# DSI_LCD.net
KiCad netlist of a schematic drawn in Altium Designer
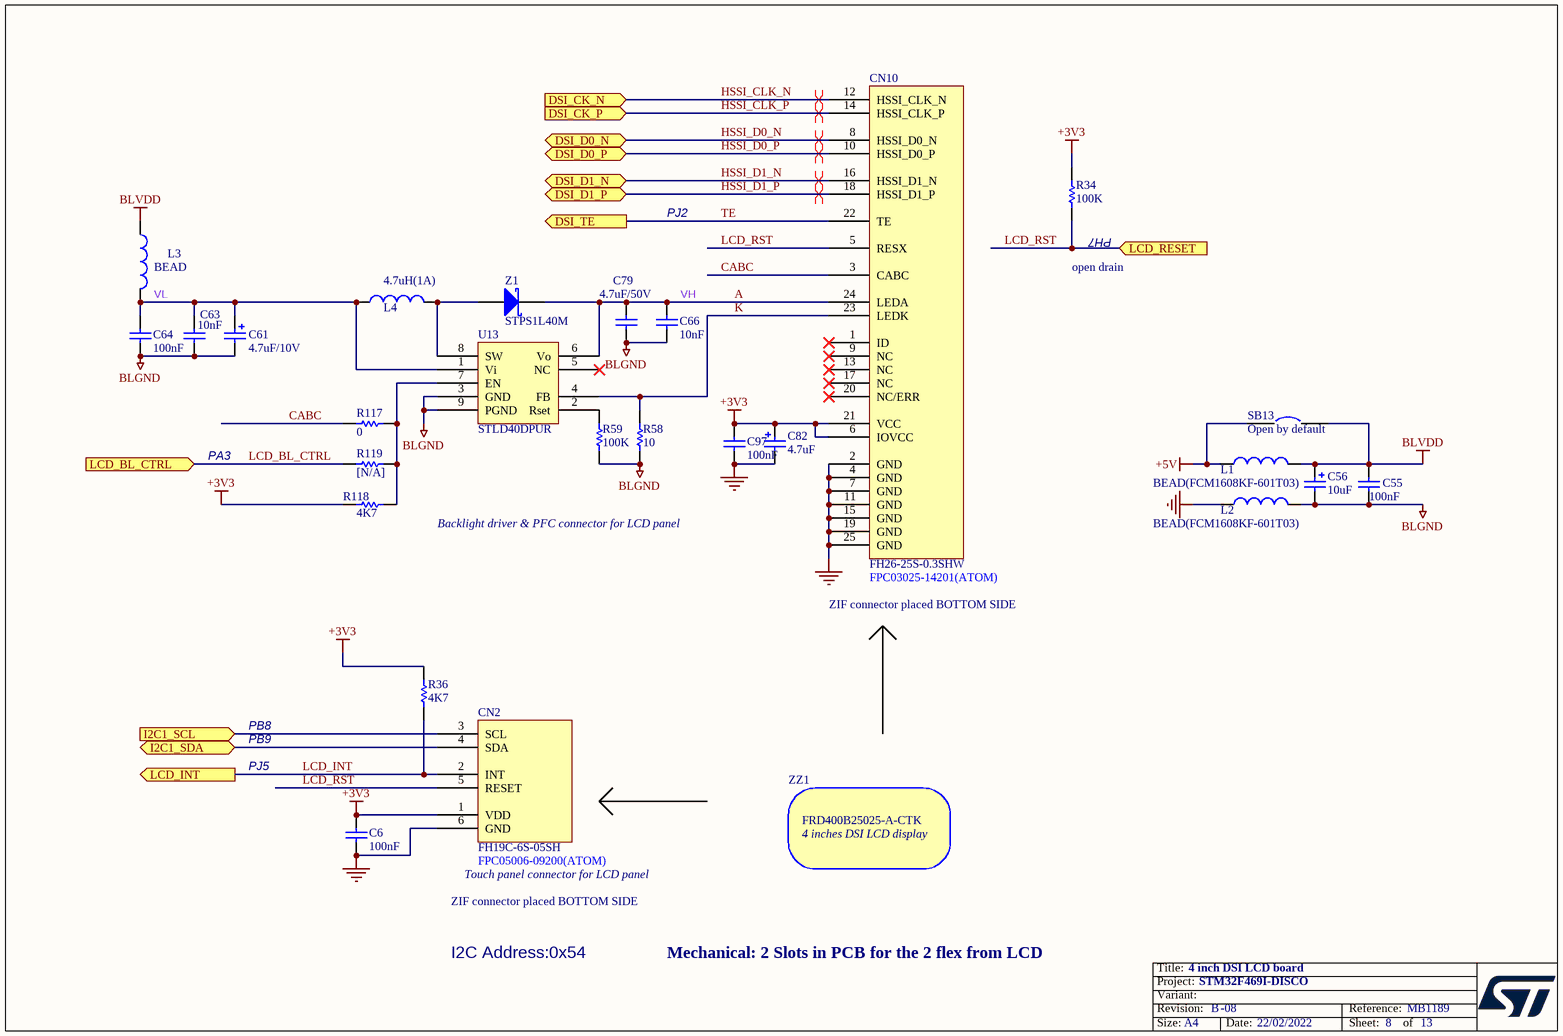
[diagram p0: DSI_LCD.SchDoc]

(export (version "E")
  (design (tool "Eeschema 10.0.6"))
  (components
    (comp (ref "C6")
      (value "100nF")
      (footprint "0402C")
      (description "Capacitor")
      (fields (field (name "PUBLISHER") "Altium Limited"))
      (libsource (lib "Miscellaneous Devices") (part "CAP"))
    )
    (comp (ref "C55")
      (value "100nF")
      (footprint "0402C")
      (description "Capacitor")
      (fields (field (name "PUBLISHER") "Altium Limited"))
      (libsource (lib "Miscellaneous Devices") (part "Cap"))
    )
    (comp (ref "C56")
      (value "10uF")
      (footprint "TAN-A")
      (description "Polarized Capacitor (Radial)")
      (fields (field (name "PUBLISHER") "Altium Limited"))
      (libsource (lib "Miscellaneous Devices") (part "Cap Pol1"))
    )
    (comp (ref "C61")
      (value "4.7uF/10V")
      (footprint "1206C")
      (description "Polarized Capacitor (Radial)")
      (fields (field (name "PUBLISHER") "Altium Limited"))
      (libsource (lib "Miscellaneous Devices") (part "Cap Pol1"))
    )
    (comp (ref "C63")
      (value "10nF")
      (footprint "0603C")
      (description "Capacitor")
      (fields (field (name "PUBLISHER") "Altium Limited"))
      (libsource (lib "Miscellaneous Devices") (part "CAP"))
    )
    (comp (ref "C64")
      (value "100nF")
      (footprint "0402C")
      (description "Capacitor")
      (fields (field (name "PUBLISHER") "Altium Limited"))
      (libsource (lib "Miscellaneous Devices") (part "CAP"))
    )
    (comp (ref "C66")
      (value "10nF")
      (footprint "0603C")
      (description "Capacitor")
      (fields (field (name "PUBLISHER") "Altium Limited"))
      (libsource (lib "*") (part "CAP"))
    )
    (comp (ref "C79")
      (value "4.7uF/50V")
      (footprint "1206C")
      (description "Capacitor")
      (fields (field (name "PUBLISHER") "Altium Limited"))
      (libsource (lib "Miscellaneous Devices") (part "CAP"))
    )
    (comp (ref "C82")
      (value "4.7uF")
      (footprint "TAN-A")
      (description "Polarized Capacitor (Radial)")
      (fields (field (name "PUBLISHER") "Altium Limited"))
      (libsource (lib "Miscellaneous Devices") (part "Cap Pol1"))
    )
    (comp (ref "C97")
      (value "100nF")
      (footprint "0402C")
      (description "Capacitor")
      (fields (field (name "PUBLISHER") "Altium Limited"))
      (libsource (lib "Miscellaneous Devices") (part "CAP"))
    )
    (comp (ref "CN2")
      (value "FH19C-6S-05SH")
      (footprint "FH19C-6S-0R5SH_FPC_CPT")
      (description "ZIF connector placed bottom side")
      (libsource (lib "MB1166") (part "FH19C-6S-05SH"))
    )
    (comp (ref "CN10")
      (value "FH26-25S-0.3SHW")
      (footprint "FPC25_FPC03025-1420")
      (description "ZIF connector placed bottom side")
      (libsource (lib "MB1166") (part "FH26-25S-0.3SHW"))
    )
    (comp (ref "L1")
      (value "BEAD(FCM1608KF-601T03)")
      (footprint "0603L")
      (description "Inductor")
      (fields (field (name "PUBLISHER") "Altium Limited"))
      (libsource (lib "Miscellaneous Devices") (part "Inductor"))
    )
    (comp (ref "L2")
      (value "BEAD(FCM1608KF-601T03)")
      (footprint "0603L")
      (description "Inductor")
      (fields (field (name "PUBLISHER") "Altium Limited"))
      (libsource (lib "Miscellaneous Devices") (part "Inductor"))
    )
    (comp (ref "L3")
      (value "BEAD")
      (footprint "0603L")
      (description "Inductor")
      (fields (field (name "PUBLISHER") "Altium Limited"))
      (libsource (lib "Miscellaneous Devices") (part "Inductor"))
    )
    (comp (ref "L4")
      (value "4.7uH(1A)")
      (footprint "1210L")
      (description "Inductor")
      (fields (field (name "PUBLISHER") "Altium Limited"))
      (libsource (lib "Miscellaneous Devices") (part "Inductor"))
    )
    (comp (ref "R34")
      (value "100K")
      (footprint "0402R")
      (description "Resistor")
      (fields (field (name "PUBLISHER") "Altium Limited"))
      (libsource (lib "Miscellaneous Devices") (part "Res1"))
    )
    (comp (ref "R36")
      (value "4K7")
      (footprint "0603R")
      (description "Resistor")
      (fields (field (name "PUBLISHER") "Altium Limited"))
      (libsource (lib "*") (part "Res1"))
    )
    (comp (ref "R58")
      (value "10")
      (footprint "0603R")
      (description "Resistor")
      (fields (field (name "PUBLISHER") "Altium Limited"))
      (libsource (lib "Miscellaneous Devices") (part "Res1"))
    )
    (comp (ref "R59")
      (value "100K")
      (footprint "0603R")
      (description "Resistor")
      (fields (field (name "PUBLISHER") "Altium Limited"))
      (libsource (lib "Miscellaneous Devices") (part "Res1"))
    )
    (comp (ref "R117")
      (value "0")
      (footprint "0603R")
      (description "Resistor")
      (fields (field (name "PUBLISHER") "Altium Limited"))
      (libsource (lib "Miscellaneous Devices") (part "Res1"))
    )
    (comp (ref "R118")
      (value "4K7")
      (footprint "0603R")
      (description "Resistor")
      (fields (field (name "PUBLISHER") "Altium Limited"))
      (libsource (lib "Miscellaneous Devices") (part "Res1"))
    )
    (comp (ref "R119")
      (value "[N/A]")
      (footprint "0603R")
      (description "Resistor")
      (fields (field (name "PUBLISHER") "Altium Limited"))
      (libsource (lib "Miscellaneous Devices") (part "Res1"))
    )
    (comp (ref "SB13")
      (value "Open by default")
      (footprint "SB_0603")
      (description "Circuit Breaker")
      (fields (field (name "PUBLISHER") "Altium Limited"))
      (libsource (lib "Miscellaneous Devices") (part "Circuit Breaker"))
    )
    (comp (ref "U13")
      (value "STLD40DPUR")
      (footprint "SON8_0R65_3X3")
      (libsource (lib "3.2LCD_daughterboard") (part "STLD40DPMR"))
    )
    (comp (ref "Z1")
      (value "STPS1L40M")
      (footprint "DO-216AA")
      (description "Schottky Diode")
      (fields (field (name "PUBLISHER") "Altium Limited"))
      (libsource (lib "Miscellaneous Devices") (part "D Schottky"))
    )
    (comp (ref "ZZ1")
      (value "FRD400B25025-A-CTK")
      (description "4 inches DSI LCD with touch screen")
      (libsource (lib "Almos") (part "BoM_Item"))
    )
  )
  (nets
    (net (code "1") (name "+3V3") (class "Default")
      (node (ref "C6") (pin "2") (pinfunction "2_2") (pintype "passive"))
      (node (ref "C82") (pin "1") (pinfunction "1_1") (pintype "passive"))
      (node (ref "C97") (pin "2") (pinfunction "2_2") (pintype "passive"))
      (node (ref "CN10") (pin "21") (pinfunction "VCC_21") (pintype "passive"))
      (node (ref "CN10") (pin "6") (pinfunction "IOVCC_6") (pintype "passive"))
      (node (ref "CN2") (pin "1") (pinfunction "VDD_1") (pintype "passive"))
      (node (ref "R118") (pin "2") (pinfunction "2_2") (pintype "passive"))
      (node (ref "R34") (pin "1") (pinfunction "1_1") (pintype "passive"))
      (node (ref "R36") (pin "1") (pinfunction "1_1") (pintype "passive"))
    )
    (net (code "2") (name "+5V") (class "Default")
      (node (ref "L1") (pin "1") (pinfunction "1_1") (pintype "passive"))
      (node (ref "SB13") (pin "1") (pinfunction "1_1") (pintype "passive"))
    )
    (net (code "3") (name "/A") (class "Default")
      (node (ref "C66") (pin "2") (pinfunction "2_2") (pintype "passive"))
      (node (ref "C79") (pin "1") (pinfunction "1_1") (pintype "passive"))
      (node (ref "CN10") (pin "24") (pinfunction "LEDA_24") (pintype "passive"))
      (node (ref "U13") (pin "6") (pinfunction "Vo_6") (pintype "passive"))
      (node (ref "Z1") (pin "2") (pinfunction "K_2") (pintype "passive"))
    )
    (net (code "4") (name "/CABC") (class "Default")
      (node (ref "CN10") (pin "3") (pinfunction "CABC_3") (pintype "passive"))
      (node (ref "R117") (pin "2") (pinfunction "2_2") (pintype "passive"))
    )
    (net (code "5") (name "/HSSI_CLK_N") (class "Default")
      (node (ref "CN10") (pin "12") (pinfunction "HSSI_CLK_N_12") (pintype "passive"))
    )
    (net (code "6") (name "/HSSI_CLK_P") (class "Default")
      (node (ref "CN10") (pin "14") (pinfunction "HSSI_CLK_P_14") (pintype "passive"))
    )
    (net (code "7") (name "/HSSI_D0_N") (class "Default")
      (node (ref "CN10") (pin "8") (pinfunction "HSSI_D0_N_8") (pintype "passive"))
    )
    (net (code "8") (name "/HSSI_D0_P") (class "Default")
      (node (ref "CN10") (pin "10") (pinfunction "HSSI_D0_P_10") (pintype "passive"))
    )
    (net (code "9") (name "/HSSI_D1_N") (class "Default")
      (node (ref "CN10") (pin "16") (pinfunction "HSSI_D1_N_16") (pintype "passive"))
    )
    (net (code "10") (name "/HSSI_D1_P") (class "Default")
      (node (ref "CN10") (pin "18") (pinfunction "HSSI_D1_P_18") (pintype "passive"))
    )
    (net (code "11") (name "/I2C1_SCL") (class "Default")
      (node (ref "CN2") (pin "3") (pinfunction "SCL_3") (pintype "passive"))
    )
    (net (code "12") (name "/I2C1_SDA") (class "Default")
      (node (ref "CN2") (pin "4") (pinfunction "SDA_4") (pintype "passive"))
    )
    (net (code "13") (name "/K") (class "Default")
      (node (ref "CN10") (pin "23") (pinfunction "LEDK_23") (pintype "passive"))
      (node (ref "R58") (pin "2") (pinfunction "2_2") (pintype "passive"))
      (node (ref "U13") (pin "4") (pinfunction "FB_4") (pintype "passive"))
    )
    (net (code "14") (name "/LCD_BL_CTRL") (class "Default")
      (node (ref "R119") (pin "2") (pinfunction "2_2") (pintype "passive"))
    )
    (net (code "15") (name "/LCD_INT") (class "Default")
      (node (ref "CN2") (pin "2") (pinfunction "INT_2") (pintype "passive"))
      (node (ref "R36") (pin "2") (pinfunction "2_2") (pintype "passive"))
    )
    (net (code "16") (name "/LCD_RST") (class "Default")
      (node (ref "CN10") (pin "5") (pinfunction "RESX_5") (pintype "passive"))
      (node (ref "CN2") (pin "5") (pinfunction "RESET_5") (pintype "passive"))
      (node (ref "R34") (pin "2") (pinfunction "2_2") (pintype "passive"))
    )
    (net (code "17") (name "/TE") (class "Default")
      (node (ref "CN10") (pin "22") (pinfunction "TE_22") (pintype "passive"))
    )
    (net (code "18") (name "/VL") (class "Default")
      (node (ref "C61") (pin "1") (pinfunction "1_1") (pintype "passive"))
      (node (ref "C63") (pin "2") (pinfunction "2_2") (pintype "passive"))
      (node (ref "C64") (pin "2") (pinfunction "2_2") (pintype "passive"))
      (node (ref "L3") (pin "2") (pinfunction "2_2") (pintype "passive"))
      (node (ref "L4") (pin "1") (pinfunction "1_1") (pintype "passive"))
      (node (ref "U13") (pin "1") (pinfunction "Vi_1") (pintype "passive"))
    )
    (net (code "19") (name "BLGND") (class "Default")
      (node (ref "C55") (pin "2") (pinfunction "2_2") (pintype "passive"))
      (node (ref "C56") (pin "2") (pinfunction "2_2") (pintype "passive"))
      (node (ref "C61") (pin "2") (pinfunction "2_2") (pintype "passive"))
      (node (ref "C63") (pin "1") (pinfunction "1_1") (pintype "passive"))
      (node (ref "C64") (pin "1") (pinfunction "1_1") (pintype "passive"))
      (node (ref "C66") (pin "1") (pinfunction "1_1") (pintype "passive"))
      (node (ref "C79") (pin "2") (pinfunction "2_2") (pintype "passive"))
      (node (ref "L2") (pin "2") (pinfunction "2_2") (pintype "passive"))
      (node (ref "R58") (pin "1") (pinfunction "1_1") (pintype "passive"))
      (node (ref "R59") (pin "2") (pinfunction "2_2") (pintype "passive"))
      (node (ref "U13") (pin "3") (pinfunction "GND_3") (pintype "passive"))
      (node (ref "U13") (pin "9") (pinfunction "PGND_9") (pintype "passive"))
    )
    (net (code "20") (name "BLVDD") (class "Default")
      (node (ref "C55") (pin "1") (pinfunction "1_1") (pintype "passive"))
      (node (ref "C56") (pin "1") (pinfunction "1_1") (pintype "passive"))
      (node (ref "L1") (pin "2") (pinfunction "2_2") (pintype "passive"))
      (node (ref "L3") (pin "1") (pinfunction "1_1") (pintype "passive"))
      (node (ref "SB13") (pin "2") (pinfunction "2_2") (pintype "passive"))
    )
    (net (code "21") (name "GND") (class "Default")
      (node (ref "C6") (pin "1") (pinfunction "1_1") (pintype "passive"))
      (node (ref "C82") (pin "2") (pinfunction "2_2") (pintype "passive"))
      (node (ref "C97") (pin "1") (pinfunction "1_1") (pintype "passive"))
      (node (ref "CN10") (pin "11") (pinfunction "GND_11") (pintype "passive"))
      (node (ref "CN10") (pin "15") (pinfunction "GND_15") (pintype "passive"))
      (node (ref "CN10") (pin "19") (pinfunction "GND_19") (pintype "passive"))
      (node (ref "CN10") (pin "2") (pinfunction "GND_2") (pintype "passive"))
      (node (ref "CN10") (pin "25") (pinfunction "GND_25") (pintype "passive"))
      (node (ref "CN10") (pin "4") (pinfunction "GND_4") (pintype "passive"))
      (node (ref "CN10") (pin "7") (pinfunction "GND_7") (pintype "passive"))
      (node (ref "CN2") (pin "6") (pinfunction "GND_6") (pintype "passive"))
      (node (ref "L2") (pin "1") (pinfunction "1_1") (pintype "passive"))
    )
    (net (code "22") (name "Net-(U13-EN)") (class "Default")
      (node (ref "R117") (pin "1") (pinfunction "1_1") (pintype "passive"))
      (node (ref "R118") (pin "1") (pinfunction "1_1") (pintype "passive"))
      (node (ref "R119") (pin "1") (pinfunction "1_1") (pintype "passive"))
      (node (ref "U13") (pin "7") (pinfunction "EN_7") (pintype "passive"))
    )
    (net (code "23") (name "Net-(U13-Rset)") (class "Default")
      (node (ref "R59") (pin "1") (pinfunction "1_1") (pintype "passive"))
      (node (ref "U13") (pin "2") (pinfunction "Rset_2") (pintype "passive"))
    )
    (net (code "24") (name "Net-(U13-SW)") (class "Default")
      (node (ref "L4") (pin "2") (pinfunction "2_2") (pintype "passive"))
      (node (ref "U13") (pin "8") (pinfunction "SW_8") (pintype "passive"))
      (node (ref "Z1") (pin "1") (pinfunction "A_1") (pintype "passive"))
    )
    (net (code "25") (name "unconnected-(CN10-ID-Pad1)") (class "Default")
      (node (ref "CN10") (pin "1") (pinfunction "ID_1") (pintype "passive+no_connect"))
    )
    (net (code "26") (name "unconnected-(CN10-NC-Pad9)") (class "Default")
      (node (ref "CN10") (pin "9") (pinfunction "NC_9") (pintype "passive+no_connect"))
    )
    (net (code "27") (name "unconnected-(CN10-NC-Pad13)") (class "Default")
      (node (ref "CN10") (pin "13") (pinfunction "NC_13") (pintype "passive+no_connect"))
    )
    (net (code "28") (name "unconnected-(CN10-NC-Pad17)") (class "Default")
      (node (ref "CN10") (pin "17") (pinfunction "NC_17") (pintype "passive+no_connect"))
    )
    (net (code "29") (name "unconnected-(CN10-NC{slash}ERR-Pad20)") (class "Default")
      (node (ref "CN10") (pin "20") (pinfunction "NC/ERR_20") (pintype "passive+no_connect"))
    )
    (net (code "30") (name "unconnected-(U13-NC-Pad5)") (class "Default")
      (node (ref "U13") (pin "5") (pinfunction "NC_5") (pintype "passive+no_connect"))
    )
  )
)
